# Xbee_Shield_V01.net
KiCad netlist of a schematic drawn in EAGLE
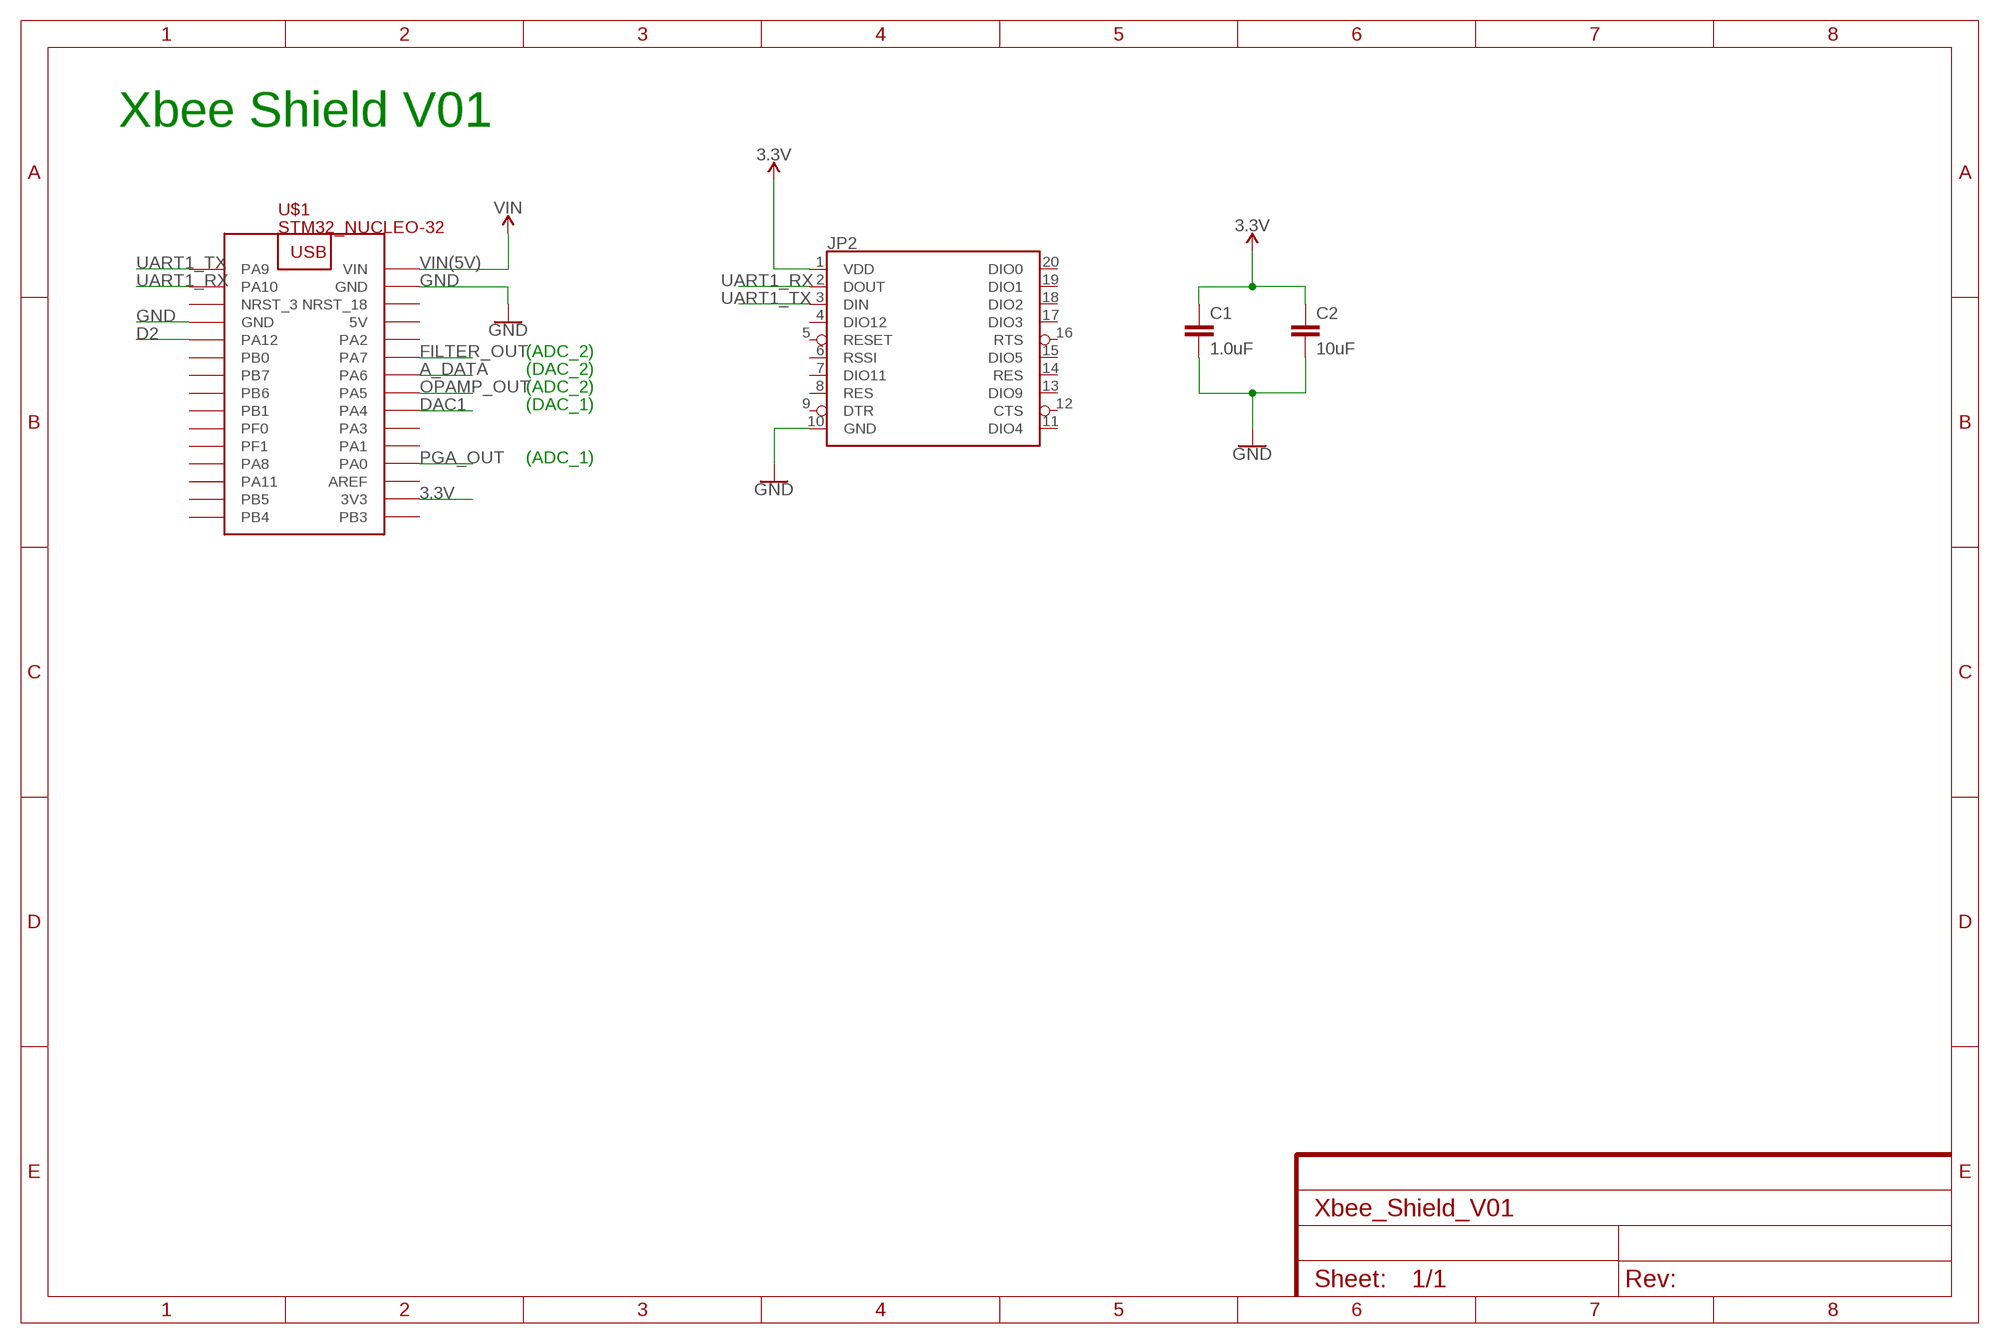
[diagram p0: schematic, sheet 1]

(export (version "E")
  (design (tool "Eeschema 10.0.6"))
  (components
    (comp (ref "C1")
      (value "1.0uF")
      (footprint "eagle-import:0805")
      (libsource (lib "eagle-import") (part "1.0UF-0805-25V-10%"))
    )
    (comp (ref "C2")
      (value "10uF")
      (footprint "eagle-import:0805")
      (libsource (lib "eagle-import") (part "1.0UF-0805-25V-10%"))
    )
    (comp (ref "JP2")
      (value "XBEESILK")
      (footprint "eagle-import:XBEE-SILK")
      (libsource (lib "eagle-import") (part "XBEESILK"))
    )
    (comp (ref "U$1")
      (value "STM32_NUCLEO-32")
      (footprint "eagle-import:STM32_NUCLEO-32")
      (libsource (lib "eagle-import") (part "STM32_NUCLEO-32"))
    )
  )
  (nets
    (net (code "1") (name "/5V") (class "Default")
      (node (ref "U$1") (pin "5V") (pinfunction "5V_5V") (pintype "power_in"))
    )
    (net (code "2") (name "/A_DATA") (class "Default")
      (node (ref "U$1") (pin "PA6") (pinfunction "PA6_PA6") (pintype "bidirectional"))
    )
    (net (code "3") (name "/D2") (class "Default")
      (node (ref "U$1") (pin "PA12") (pinfunction "PA12_PA12") (pintype "bidirectional"))
    )
    (net (code "4") (name "/DAC1") (class "Default")
      (node (ref "U$1") (pin "PA4") (pinfunction "PA4_PA4") (pintype "bidirectional"))
    )
    (net (code "5") (name "/FILTER_OUT") (class "Default")
      (node (ref "U$1") (pin "PA7") (pinfunction "PA7_PA7") (pintype "bidirectional"))
    )
    (net (code "6") (name "/OPAMP_OUT") (class "Default")
      (node (ref "U$1") (pin "PA5") (pinfunction "PA5_PA5") (pintype "bidirectional"))
    )
    (net (code "7") (name "/PGA_OUT") (class "Default")
      (node (ref "U$1") (pin "PA0") (pinfunction "PA0_PA0") (pintype "bidirectional"))
    )
    (net (code "8") (name "/UART1_RX") (class "Default")
      (node (ref "JP2") (pin "2") (pinfunction "DOUT_2") (pintype "output"))
      (node (ref "U$1") (pin "PA10") (pinfunction "PA10_PA10") (pintype "bidirectional"))
    )
    (net (code "9") (name "/UART1_TX") (class "Default")
      (node (ref "JP2") (pin "3") (pinfunction "DIN_3") (pintype "input"))
      (node (ref "U$1") (pin "PA9") (pinfunction "PA9_PA9") (pintype "bidirectional"))
    )
    (net (code "10") (name "3.3V") (class "Default")
      (node (ref "C1") (pin "1") (pinfunction "1_1") (pintype "passive"))
      (node (ref "C2") (pin "1") (pinfunction "1_1") (pintype "passive"))
      (node (ref "JP2") (pin "1") (pinfunction "VDD_1") (pintype "power_in"))
      (node (ref "U$1") (pin "3V3") (pinfunction "3V3_3V3") (pintype "power_in"))
    )
    (net (code "11") (name "GND") (class "Default")
      (node (ref "C1") (pin "2") (pinfunction "2_2") (pintype "passive"))
      (node (ref "C2") (pin "2") (pinfunction "2_2") (pintype "passive"))
      (node (ref "JP2") (pin "10") (pinfunction "GND_10") (pintype "power_in"))
      (node (ref "U$1") (pin "GND@17") (pinfunction "GND_GND@17") (pintype "power_in"))
      (node (ref "U$1") (pin "GND@4") (pinfunction "GND_GND@4") (pintype "power_in"))
    )
    (net (code "12") (name "VIN") (class "Default")
      (node (ref "U$1") (pin "VIN") (pinfunction "VIN_VIN") (pintype "power_in"))
    )
    (net (code "13") (name "unconnected-(JP2-CTS-Pad12)") (class "Default")
      (node (ref "JP2") (pin "12") (pinfunction "CTS_12") (pintype "output"))
    )
    (net (code "14") (name "unconnected-(JP2-DIO0-Pad20)") (class "Default")
      (node (ref "JP2") (pin "20") (pinfunction "DIO0_20") (pintype "bidirectional"))
    )
    (net (code "15") (name "unconnected-(JP2-DIO1-Pad19)") (class "Default")
      (node (ref "JP2") (pin "19") (pinfunction "DIO1_19") (pintype "bidirectional"))
    )
    (net (code "16") (name "unconnected-(JP2-DIO2-Pad18)") (class "Default")
      (node (ref "JP2") (pin "18") (pinfunction "DIO2_18") (pintype "bidirectional"))
    )
    (net (code "17") (name "unconnected-(JP2-DIO3-Pad17)") (class "Default")
      (node (ref "JP2") (pin "17") (pinfunction "DIO3_17") (pintype "bidirectional"))
    )
    (net (code "18") (name "unconnected-(JP2-DIO4-Pad11)") (class "Default")
      (node (ref "JP2") (pin "11") (pinfunction "DIO4_11") (pintype "bidirectional"))
    )
    (net (code "19") (name "unconnected-(JP2-DIO5-Pad15)") (class "Default")
      (node (ref "JP2") (pin "15") (pinfunction "DIO5_15") (pintype "bidirectional"))
    )
    (net (code "20") (name "unconnected-(JP2-DIO9-Pad13)") (class "Default")
      (node (ref "JP2") (pin "13") (pinfunction "DIO9_13") (pintype "bidirectional"))
    )
    (net (code "21") (name "unconnected-(JP2-DIO11-Pad7)") (class "Default")
      (node (ref "JP2") (pin "7") (pinfunction "DIO11_7") (pintype "bidirectional"))
    )
    (net (code "22") (name "unconnected-(JP2-DIO12-Pad4)") (class "Default")
      (node (ref "JP2") (pin "4") (pinfunction "DIO12_4") (pintype "bidirectional"))
    )
    (net (code "23") (name "unconnected-(JP2-DTR-Pad9)") (class "Default")
      (node (ref "JP2") (pin "9") (pinfunction "DTR_9") (pintype "bidirectional"))
    )
    (net (code "24") (name "unconnected-(JP2-RES-Pad8)") (class "Default")
      (node (ref "JP2") (pin "8") (pinfunction "RES_8") (pintype "bidirectional"))
    )
    (net (code "25") (name "unconnected-(JP2-RES-Pad14)") (class "Default")
      (node (ref "JP2") (pin "14") (pinfunction "RES_14") (pintype "bidirectional"))
    )
    (net (code "26") (name "unconnected-(JP2-RESET-Pad5)") (class "Default")
      (node (ref "JP2") (pin "5") (pinfunction "RESET_5") (pintype "input"))
    )
    (net (code "27") (name "unconnected-(JP2-RSSI-Pad6)") (class "Default")
      (node (ref "JP2") (pin "6") (pinfunction "RSSI_6") (pintype "bidirectional"))
    )
    (net (code "28") (name "unconnected-(JP2-RTS-Pad16)") (class "Default")
      (node (ref "JP2") (pin "16") (pinfunction "RTS_16") (pintype "input"))
    )
    (net (code "29") (name "unconnected-(U$1-PadAREF)") (class "Default")
      (node (ref "U$1") (pin "AREF") (pinfunction "AREF_AREF") (pintype "bidirectional"))
    )
    (net (code "30") (name "unconnected-(U$1-PadNRST_3)") (class "Default")
      (node (ref "U$1") (pin "NRST_3") (pinfunction "NRST_3_NRST_3") (pintype "bidirectional"))
    )
    (net (code "31") (name "unconnected-(U$1-PadNRST_18)") (class "Default")
      (node (ref "U$1") (pin "NRST_18") (pinfunction "NRST_18_NRST_18") (pintype "bidirectional"))
    )
    (net (code "32") (name "unconnected-(U$1-PadPA1)") (class "Default")
      (node (ref "U$1") (pin "PA1") (pinfunction "PA1_PA1") (pintype "bidirectional"))
    )
    (net (code "33") (name "unconnected-(U$1-PadPA2)") (class "Default")
      (node (ref "U$1") (pin "PA2") (pinfunction "PA2_PA2") (pintype "bidirectional"))
    )
    (net (code "34") (name "unconnected-(U$1-PadPA3)") (class "Default")
      (node (ref "U$1") (pin "PA3") (pinfunction "PA3_PA3") (pintype "bidirectional"))
    )
    (net (code "35") (name "unconnected-(U$1-PadPA8)") (class "Default")
      (node (ref "U$1") (pin "PA8") (pinfunction "PA8_PA8") (pintype "bidirectional"))
    )
    (net (code "36") (name "unconnected-(U$1-PadPA11)") (class "Default")
      (node (ref "U$1") (pin "PA11") (pinfunction "PA11_PA11") (pintype "bidirectional"))
    )
    (net (code "37") (name "unconnected-(U$1-PadPB0)") (class "Default")
      (node (ref "U$1") (pin "PB0") (pinfunction "PB0_PB0") (pintype "bidirectional"))
    )
    (net (code "38") (name "unconnected-(U$1-PadPB1)") (class "Default")
      (node (ref "U$1") (pin "PB1") (pinfunction "PB1_PB1") (pintype "bidirectional"))
    )
    (net (code "39") (name "unconnected-(U$1-PadPB3)") (class "Default")
      (node (ref "U$1") (pin "PB3") (pinfunction "PB3_PB3") (pintype "bidirectional"))
    )
    (net (code "40") (name "unconnected-(U$1-PadPB4)") (class "Default")
      (node (ref "U$1") (pin "PB4") (pinfunction "PB4_PB4") (pintype "bidirectional"))
    )
    (net (code "41") (name "unconnected-(U$1-PadPB5)") (class "Default")
      (node (ref "U$1") (pin "PB5") (pinfunction "PB5_PB5") (pintype "bidirectional"))
    )
    (net (code "42") (name "unconnected-(U$1-PadPB6)") (class "Default")
      (node (ref "U$1") (pin "PB6") (pinfunction "PB6_PB6") (pintype "bidirectional"))
    )
    (net (code "43") (name "unconnected-(U$1-PadPB7)") (class "Default")
      (node (ref "U$1") (pin "PB7") (pinfunction "PB7_PB7") (pintype "bidirectional"))
    )
    (net (code "44") (name "unconnected-(U$1-PadPF0)") (class "Default")
      (node (ref "U$1") (pin "PF0") (pinfunction "PF0_PF0") (pintype "bidirectional"))
    )
    (net (code "45") (name "unconnected-(U$1-PadPF1)") (class "Default")
      (node (ref "U$1") (pin "PF1") (pinfunction "PF1_PF1") (pintype "bidirectional"))
    )
  )
)
